# Drivers.net
KiCad netlist of a schematic drawn in Altium Designer
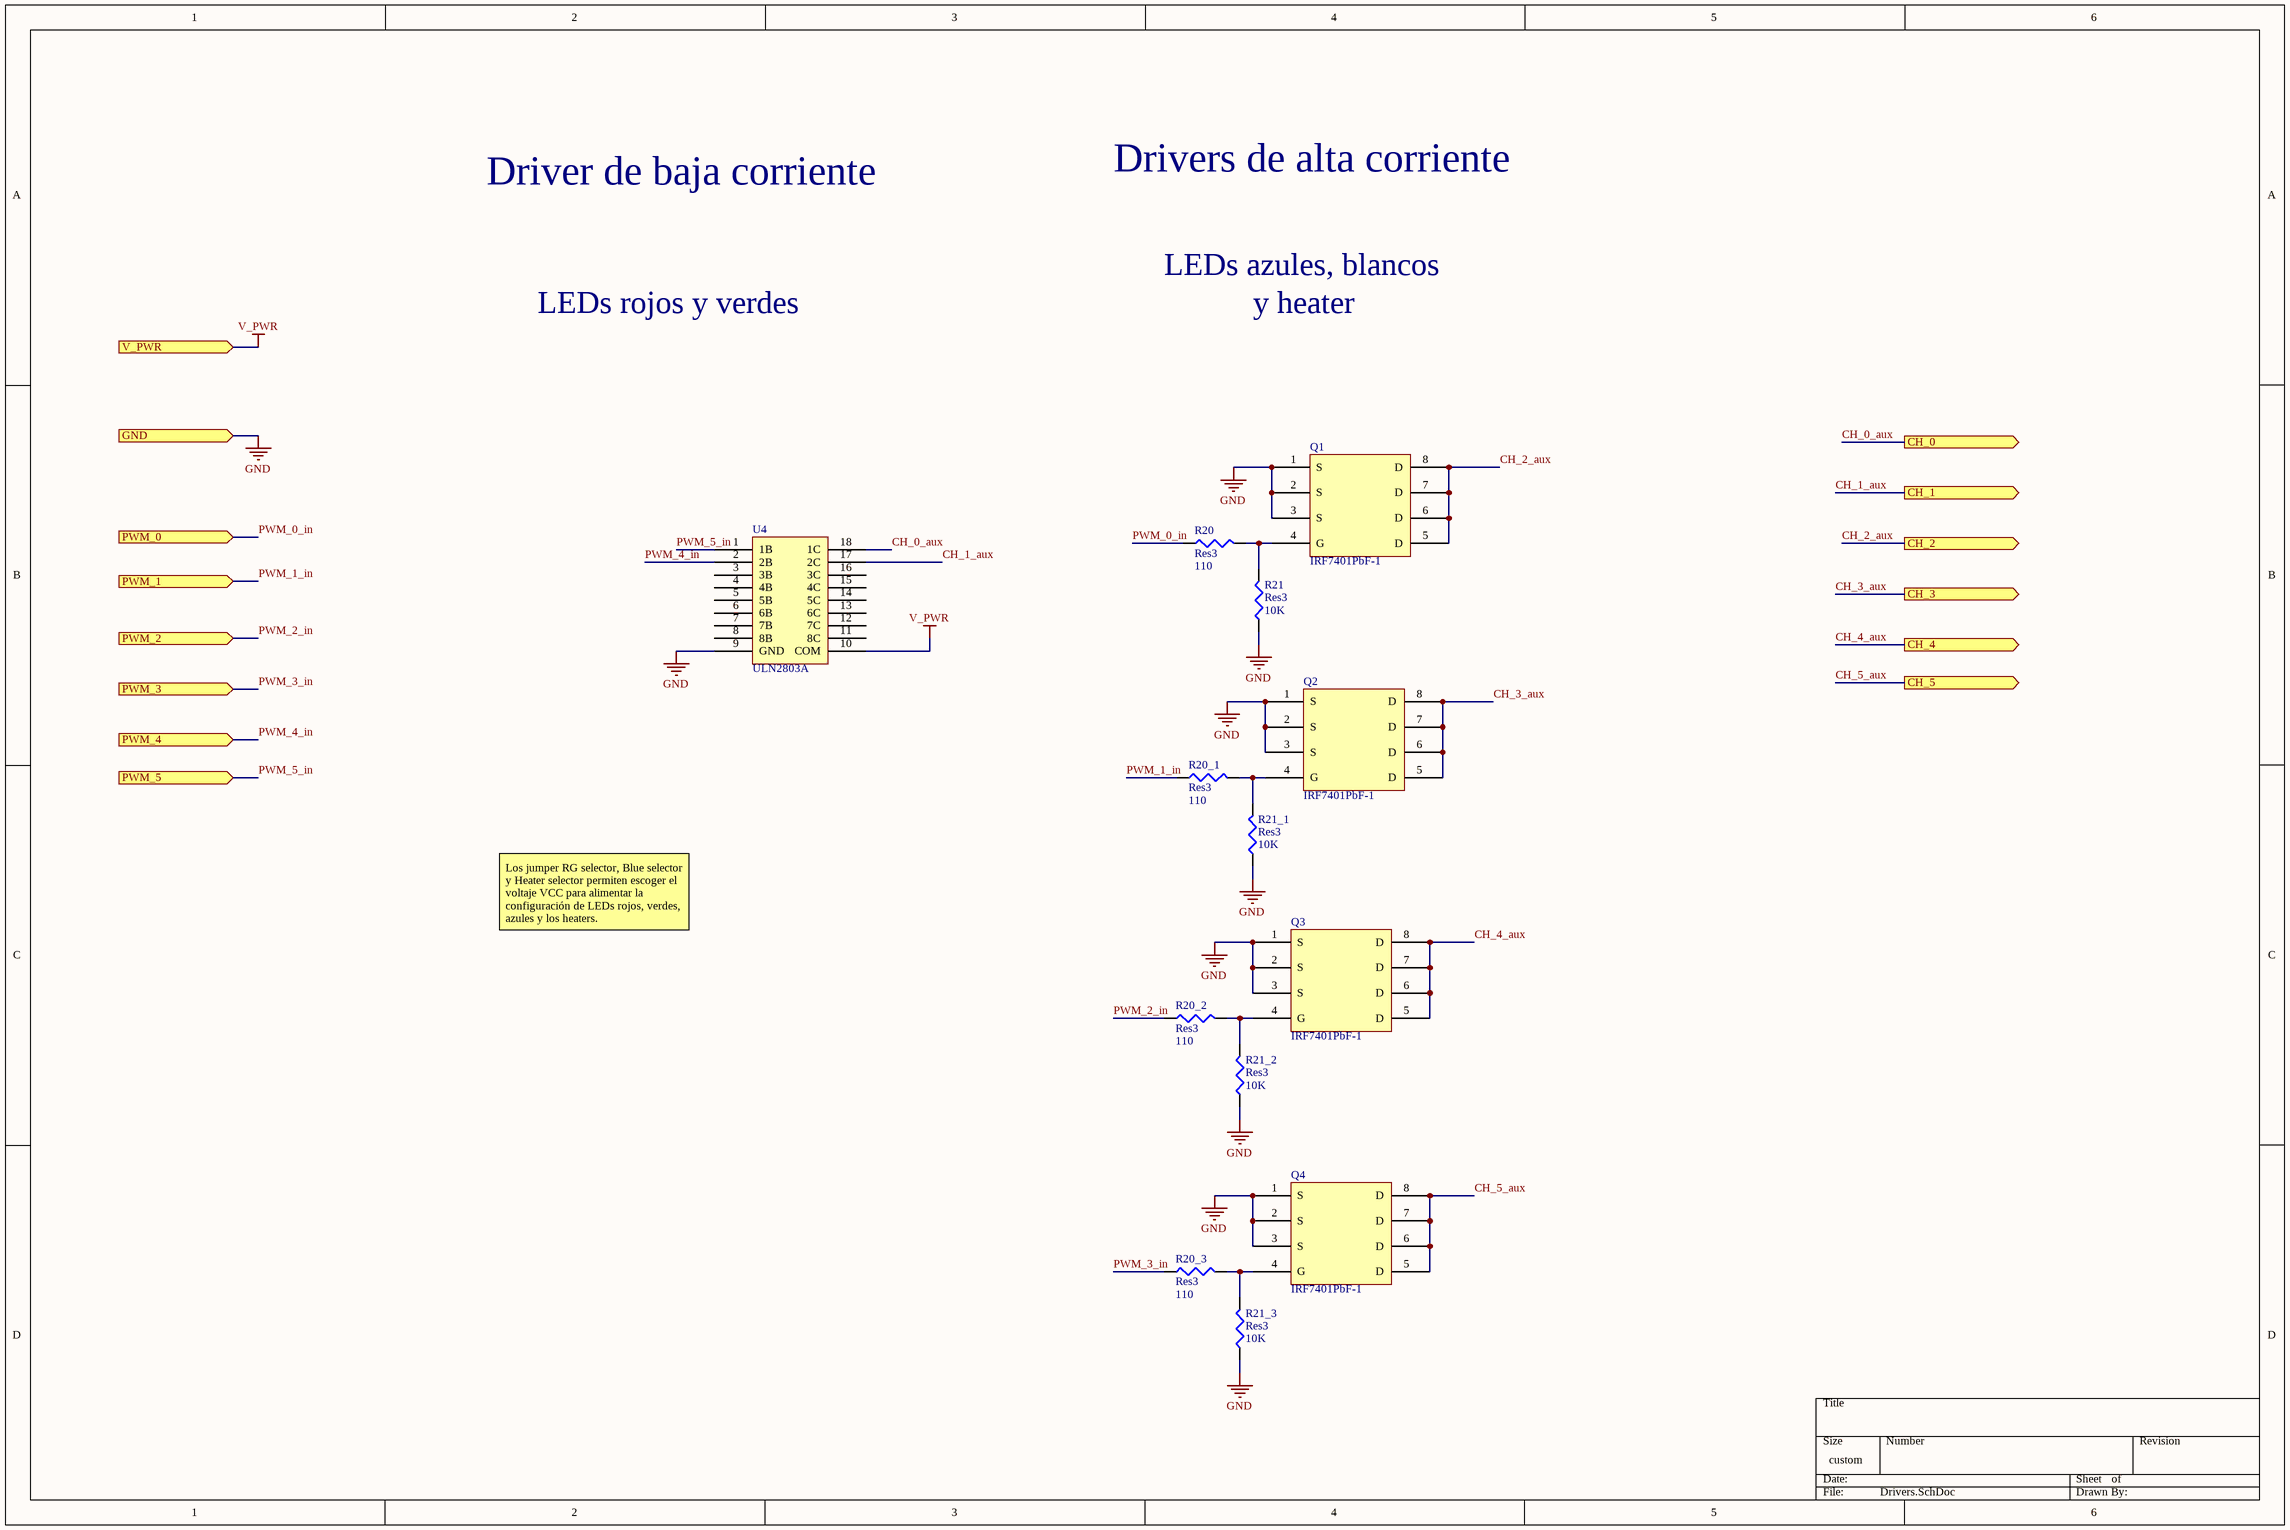
[diagram p0: Drivers.SchDoc]

(export (version "E")
  (design (tool "Eeschema 10.0.6"))
  (components
    (comp (ref "Q1")
      (value "IRF7401PbF-1")
      (footprint "SOIC8")
      (description "MOSFET N Channel 20V 8.7A 700mV @ 250uA 22mΩ @ 4.1A,4.5V SOIC-8_150mil RoHS")
      (fields
        (field (name "MANUFACTURER") "Infineon Technologies")
        (field (name "MANUFACTURER PART NUMBER") "IRF7401TRPBF")
      )
      (libsource (lib "IoWLabs") (part "IRF7401"))
    )
    (comp (ref "Q2")
      (value "IRF7401PbF-1")
      (footprint "SOIC8")
      (description "MOSFET N Channel 20V 8.7A 700mV @ 250uA 22mΩ @ 4.1A,4.5V SOIC-8_150mil RoHS")
      (fields
        (field (name "MANUFACTURER") "Infineon Technologies")
        (field (name "MANUFACTURER PART NUMBER") "IRF7401TRPBF")
      )
      (libsource (lib "IoWLabs") (part "IRF7401"))
    )
    (comp (ref "Q3")
      (value "IRF7401PbF-1")
      (footprint "SOIC8")
      (description "MOSFET N Channel 20V 8.7A 700mV @ 250uA 22mΩ @ 4.1A,4.5V SOIC-8_150mil RoHS")
      (fields
        (field (name "MANUFACTURER") "Infineon Technologies")
        (field (name "MANUFACTURER PART NUMBER") "IRF7401TRPBF")
      )
      (libsource (lib "IoWLabs") (part "IRF7401"))
    )
    (comp (ref "Q4")
      (value "IRF7401PbF-1")
      (footprint "SOIC8")
      (description "MOSFET N Channel 20V 8.7A 700mV @ 250uA 22mΩ @ 4.1A,4.5V SOIC-8_150mil RoHS")
      (fields
        (field (name "MANUFACTURER") "Infineon Technologies")
        (field (name "MANUFACTURER PART NUMBER") "IRF7401TRPBF")
      )
      (libsource (lib "IoWLabs") (part "IRF7401"))
    )
    (comp (ref "R20")
      (value "Res3")
      (footprint "J1-0603")
      (description "Resistor")
      (fields
        (field (name "ALTIUM_VALUE") "110")
        (field (name "MANUFACTURER") "ROHM Semicon")
        (field (name "MANUFACTURER PART NUMBER") "MCR03EZPFX1100")
        (field (name "PUBLISHER") "Altium Limited")
      )
      (libsource (lib "Miscellaneous Devices") (part "Res3"))
    )
    (comp (ref "R20_1")
      (value "Res3")
      (footprint "J1-0603")
      (description "Resistor")
      (fields
        (field (name "ALTIUM_VALUE") "110")
        (field (name "MANUFACTURER") "ROHM Semicon")
        (field (name "MANUFACTURER PART NUMBER") "MCR03EZPFX1100")
        (field (name "PUBLISHER") "Altium Limited")
      )
      (libsource (lib "Miscellaneous Devices") (part "Res3"))
    )
    (comp (ref "R20_2")
      (value "Res3")
      (footprint "J1-0603")
      (description "Resistor")
      (fields
        (field (name "ALTIUM_VALUE") "110")
        (field (name "MANUFACTURER") "ROHM Semicon")
        (field (name "MANUFACTURER PART NUMBER") "MCR03EZPFX1100")
        (field (name "PUBLISHER") "Altium Limited")
      )
      (libsource (lib "Miscellaneous Devices") (part "Res3"))
    )
    (comp (ref "R20_3")
      (value "Res3")
      (footprint "J1-0603")
      (description "Resistor")
      (fields
        (field (name "ALTIUM_VALUE") "110")
        (field (name "MANUFACTURER") "ROHM Semicon")
        (field (name "MANUFACTURER PART NUMBER") "MCR03EZPFX1100")
        (field (name "PUBLISHER") "Altium Limited")
      )
      (libsource (lib "Miscellaneous Devices") (part "Res3"))
    )
    (comp (ref "R21")
      (value "Res3")
      (footprint "J1-0603")
      (description "Resistor")
      (fields
        (field (name "ALTIUM_VALUE") "10K")
        (field (name "MANUFACTURER") "PANASONIC")
        (field (name "MANUFACTURER PART NUMBER") "ERJPA3F1002V")
        (field (name "PUBLISHER") "Altium Limited")
      )
      (libsource (lib "Miscellaneous Devices") (part "Res3"))
    )
    (comp (ref "R21_1")
      (value "Res3")
      (footprint "J1-0603")
      (description "Resistor")
      (fields
        (field (name "ALTIUM_VALUE") "10K")
        (field (name "MANUFACTURER") "PANASONIC")
        (field (name "MANUFACTURER PART NUMBER") "ERJPA3F1002V")
        (field (name "PUBLISHER") "Altium Limited")
      )
      (libsource (lib "Miscellaneous Devices") (part "Res3"))
    )
    (comp (ref "R21_2")
      (value "Res3")
      (footprint "J1-0603")
      (description "Resistor")
      (fields
        (field (name "ALTIUM_VALUE") "10K")
        (field (name "MANUFACTURER") "PANASONIC")
        (field (name "MANUFACTURER PART NUMBER") "ERJPA3F1002V")
        (field (name "PUBLISHER") "Altium Limited")
      )
      (libsource (lib "Miscellaneous Devices") (part "Res3"))
    )
    (comp (ref "R21_3")
      (value "Res3")
      (footprint "J1-0603")
      (description "Resistor")
      (fields
        (field (name "ALTIUM_VALUE") "10K")
        (field (name "MANUFACTURER") "PANASONIC")
        (field (name "MANUFACTURER PART NUMBER") "ERJPA3F1002V")
        (field (name "PUBLISHER") "Altium Limited")
      )
      (libsource (lib "Miscellaneous Devices") (part "Res3"))
    )
    (comp (ref "U4")
      (value "ULN2803A")
      (footprint "SOIC18")
      (description "Darlington transistor array driver SOIC-18_300mi")
      (fields
        (field (name "MANUFACTURER") "Texas instrument")
        (field (name "MANUFACTURER PART NUMBER") "ULN2803ADWR")
      )
      (libsource (lib "IoWLabs") (part "ULN2803"))
    )
  )
  (nets
    (net (code "1") (name "/CH_0_aux") (class "Default")
      (node (ref "U4") (pin "18") (pinfunction "1C_18") (pintype "passive"))
    )
    (net (code "2") (name "/CH_1_aux") (class "Default")
      (node (ref "U4") (pin "17") (pinfunction "2C_17") (pintype "passive"))
    )
    (net (code "3") (name "/CH_2_aux") (class "Default")
      (node (ref "Q1") (pin "5") (pinfunction "D_5") (pintype "passive"))
      (node (ref "Q1") (pin "6") (pinfunction "D_6") (pintype "passive"))
      (node (ref "Q1") (pin "7") (pinfunction "D_7") (pintype "passive"))
      (node (ref "Q1") (pin "8") (pinfunction "D_8") (pintype "passive"))
    )
    (net (code "4") (name "/CH_3_aux") (class "Default")
      (node (ref "Q2") (pin "5") (pinfunction "D_5") (pintype "passive"))
      (node (ref "Q2") (pin "6") (pinfunction "D_6") (pintype "passive"))
      (node (ref "Q2") (pin "7") (pinfunction "D_7") (pintype "passive"))
      (node (ref "Q2") (pin "8") (pinfunction "D_8") (pintype "passive"))
    )
    (net (code "5") (name "/CH_4_aux") (class "Default")
      (node (ref "Q3") (pin "5") (pinfunction "D_5") (pintype "passive"))
      (node (ref "Q3") (pin "6") (pinfunction "D_6") (pintype "passive"))
      (node (ref "Q3") (pin "7") (pinfunction "D_7") (pintype "passive"))
      (node (ref "Q3") (pin "8") (pinfunction "D_8") (pintype "passive"))
    )
    (net (code "6") (name "/CH_5_aux") (class "Default")
      (node (ref "Q4") (pin "5") (pinfunction "D_5") (pintype "passive"))
      (node (ref "Q4") (pin "6") (pinfunction "D_6") (pintype "passive"))
      (node (ref "Q4") (pin "7") (pinfunction "D_7") (pintype "passive"))
      (node (ref "Q4") (pin "8") (pinfunction "D_8") (pintype "passive"))
    )
    (net (code "7") (name "/PWM_0_in") (class "Default")
      (node (ref "R20") (pin "1") (pinfunction "1_1") (pintype "passive"))
    )
    (net (code "8") (name "/PWM_1_in") (class "Default")
      (node (ref "R20_1") (pin "1") (pinfunction "1_1") (pintype "passive"))
    )
    (net (code "9") (name "/PWM_2_in") (class "Default")
      (node (ref "R20_2") (pin "1") (pinfunction "1_1") (pintype "passive"))
    )
    (net (code "10") (name "/PWM_3_in") (class "Default")
      (node (ref "R20_3") (pin "1") (pinfunction "1_1") (pintype "passive"))
    )
    (net (code "11") (name "/PWM_4_in") (class "Default")
      (node (ref "U4") (pin "2") (pinfunction "2B_2") (pintype "passive"))
    )
    (net (code "12") (name "/PWM_5_in") (class "Default")
      (node (ref "U4") (pin "1") (pinfunction "1B_1") (pintype "passive"))
    )
    (net (code "13") (name "GND") (class "Default")
      (node (ref "Q1") (pin "1") (pinfunction "S_1") (pintype "passive"))
      (node (ref "Q1") (pin "2") (pinfunction "S_2") (pintype "passive"))
      (node (ref "Q1") (pin "3") (pinfunction "S_3") (pintype "passive"))
      (node (ref "Q2") (pin "1") (pinfunction "S_1") (pintype "passive"))
      (node (ref "Q2") (pin "2") (pinfunction "S_2") (pintype "passive"))
      (node (ref "Q2") (pin "3") (pinfunction "S_3") (pintype "passive"))
      (node (ref "Q3") (pin "1") (pinfunction "S_1") (pintype "passive"))
      (node (ref "Q3") (pin "2") (pinfunction "S_2") (pintype "passive"))
      (node (ref "Q3") (pin "3") (pinfunction "S_3") (pintype "passive"))
      (node (ref "Q4") (pin "1") (pinfunction "S_1") (pintype "passive"))
      (node (ref "Q4") (pin "2") (pinfunction "S_2") (pintype "passive"))
      (node (ref "Q4") (pin "3") (pinfunction "S_3") (pintype "passive"))
      (node (ref "R21") (pin "1") (pinfunction "1_1") (pintype "passive"))
      (node (ref "R21_1") (pin "1") (pinfunction "1_1") (pintype "passive"))
      (node (ref "R21_2") (pin "1") (pinfunction "1_1") (pintype "passive"))
      (node (ref "R21_3") (pin "1") (pinfunction "1_1") (pintype "passive"))
      (node (ref "U4") (pin "9") (pinfunction "GND_9") (pintype "passive"))
    )
    (net (code "14") (name "Net-(Q1-G)") (class "Default")
      (node (ref "Q1") (pin "4") (pinfunction "G_4") (pintype "passive"))
      (node (ref "R20") (pin "2") (pinfunction "2_2") (pintype "passive"))
      (node (ref "R21") (pin "2") (pinfunction "2_2") (pintype "passive"))
    )
    (net (code "15") (name "Net-(Q2-G)") (class "Default")
      (node (ref "Q2") (pin "4") (pinfunction "G_4") (pintype "passive"))
      (node (ref "R20_1") (pin "2") (pinfunction "2_2") (pintype "passive"))
      (node (ref "R21_1") (pin "2") (pinfunction "2_2") (pintype "passive"))
    )
    (net (code "16") (name "Net-(Q3-G)") (class "Default")
      (node (ref "Q3") (pin "4") (pinfunction "G_4") (pintype "passive"))
      (node (ref "R20_2") (pin "2") (pinfunction "2_2") (pintype "passive"))
      (node (ref "R21_2") (pin "2") (pinfunction "2_2") (pintype "passive"))
    )
    (net (code "17") (name "Net-(Q4-G)") (class "Default")
      (node (ref "Q4") (pin "4") (pinfunction "G_4") (pintype "passive"))
      (node (ref "R20_3") (pin "2") (pinfunction "2_2") (pintype "passive"))
      (node (ref "R21_3") (pin "2") (pinfunction "2_2") (pintype "passive"))
    )
    (net (code "18") (name "V_PWR") (class "Default")
      (node (ref "U4") (pin "10") (pinfunction "COM_10") (pintype "passive"))
    )
    (net (code "19") (name "unconnected-(U4-3B-Pad3)") (class "Default")
      (node (ref "U4") (pin "3") (pinfunction "3B_3") (pintype "passive"))
    )
    (net (code "20") (name "unconnected-(U4-3C-Pad16)") (class "Default")
      (node (ref "U4") (pin "16") (pinfunction "3C_16") (pintype "passive"))
    )
    (net (code "21") (name "unconnected-(U4-4B-Pad4)") (class "Default")
      (node (ref "U4") (pin "4") (pinfunction "4B_4") (pintype "passive"))
    )
    (net (code "22") (name "unconnected-(U4-4C-Pad15)") (class "Default")
      (node (ref "U4") (pin "15") (pinfunction "4C_15") (pintype "passive"))
    )
    (net (code "23") (name "unconnected-(U4-5B-Pad5)") (class "Default")
      (node (ref "U4") (pin "5") (pinfunction "5B_5") (pintype "passive"))
    )
    (net (code "24") (name "unconnected-(U4-5C-Pad14)") (class "Default")
      (node (ref "U4") (pin "14") (pinfunction "5C_14") (pintype "passive"))
    )
    (net (code "25") (name "unconnected-(U4-6B-Pad6)") (class "Default")
      (node (ref "U4") (pin "6") (pinfunction "6B_6") (pintype "passive"))
    )
    (net (code "26") (name "unconnected-(U4-6C-Pad13)") (class "Default")
      (node (ref "U4") (pin "13") (pinfunction "6C_13") (pintype "passive"))
    )
    (net (code "27") (name "unconnected-(U4-7B-Pad7)") (class "Default")
      (node (ref "U4") (pin "7") (pinfunction "7B_7") (pintype "passive"))
    )
    (net (code "28") (name "unconnected-(U4-7C-Pad12)") (class "Default")
      (node (ref "U4") (pin "12") (pinfunction "7C_12") (pintype "passive"))
    )
    (net (code "29") (name "unconnected-(U4-8B-Pad8)") (class "Default")
      (node (ref "U4") (pin "8") (pinfunction "8B_8") (pintype "passive"))
    )
    (net (code "30") (name "unconnected-(U4-8C-Pad11)") (class "Default")
      (node (ref "U4") (pin "11") (pinfunction "8C_11") (pintype "passive"))
    )
  )
)
